# FTDI44.net
KiCad netlist of a schematic drawn in EAGLE
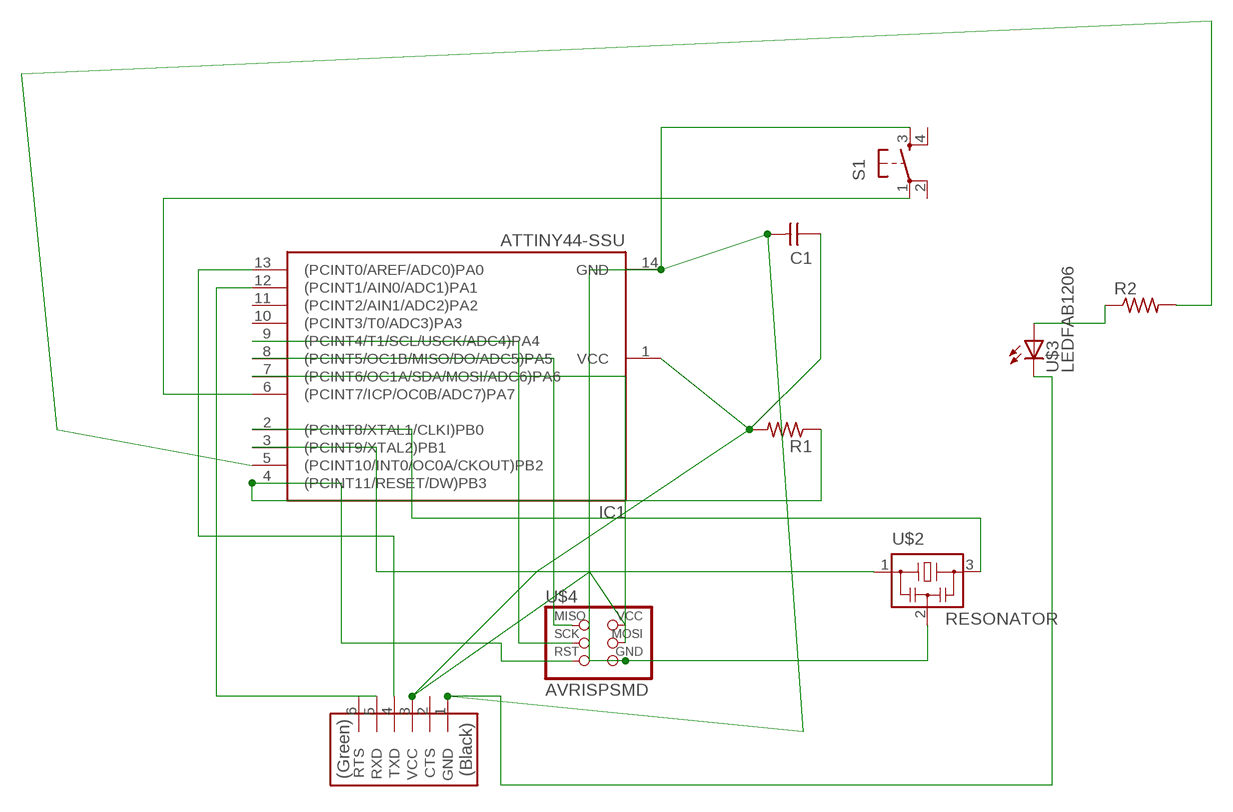
[diagram p0: schematic, sheet 1]

(export (version "E")
  (design (tool "Eeschema 10.0.6"))
  (components
    (comp (ref "C1")
      (value "CAP-UNPOLARIZEDFAB")
      (footprint "eagle-import:C1206FAB")
      (libsource (lib "eagle-import") (part "CAP-UNPOLARIZEDFAB"))
    )
    (comp (ref "IC1")
      (value "ATTINY44-SSU")
      (footprint "eagle-import:SOIC14")
      (libsource (lib "eagle-import") (part "ATTINY44-SSU"))
    )
    (comp (ref "R1")
      (value "RES-US1206FAB")
      (footprint "eagle-import:R1206FAB")
      (libsource (lib "eagle-import") (part "fab_RES-US1206FAB"))
    )
    (comp (ref "R2")
      (value "RES-US1206FAB")
      (footprint "eagle-import:R1206FAB")
      (libsource (lib "eagle-import") (part "RES-US1206FAB"))
    )
    (comp (ref "S1")
      (value "6MM_SWITCH6MM_SWITCH")
      (footprint "eagle-import:6MM_SWITCH")
      (libsource (lib "eagle-import") (part "6MM_SWITCH6MM_SWITCH"))
    )
    (comp (ref "U$1")
      (value "FTDI-SMD-HEADER")
      (footprint "eagle-import:1X06SMD")
      (libsource (lib "eagle-import") (part "FTDI-SMD-HEADER"))
    )
    (comp (ref "U$2")
      (value "RESONATOR")
      (footprint "eagle-import:EFOBM")
      (libsource (lib "eagle-import") (part "RESONATOR"))
    )
    (comp (ref "U$3")
      (value "LEDFAB1206")
      (footprint "eagle-import:LED1206FAB")
      (libsource (lib "eagle-import") (part "LEDFAB1206"))
    )
    (comp (ref "U$4")
      (value "AVRISPSMD")
      (footprint "eagle-import:2X03SMD")
      (libsource (lib "eagle-import") (part "AVRISPSMD"))
    )
  )
  (nets
    (net (code "1") (name "Net-(IC1-(PCINT0{slash}AREF{slash}ADC0)PA0)") (class "Default")
      (node (ref "IC1") (pin "13") (pinfunction "(PCINT0/AREF/ADC0)PA0_13") (pintype "bidirectional"))
      (node (ref "U$1") (pin "4") (pinfunction "TXD_4") (pintype "bidirectional"))
    )
    (net (code "2") (name "Net-(IC1-(PCINT1{slash}AIN0{slash}ADC1)PA1)") (class "Default")
      (node (ref "IC1") (pin "12") (pinfunction "(PCINT1/AIN0/ADC1)PA1_12") (pintype "bidirectional"))
      (node (ref "U$1") (pin "5") (pinfunction "RXD_5") (pintype "bidirectional"))
    )
    (net (code "3") (name "Net-(IC1-(PCINT4{slash}T1{slash}SCL{slash}USCK{slash}ADC4)PA4)") (class "Default")
      (node (ref "IC1") (pin "9") (pinfunction "(PCINT4/T1/SCL/USCK/ADC4)PA4_9") (pintype "bidirectional"))
      (node (ref "U$4") (pin "3") (pinfunction "SCK_3") (pintype "passive"))
    )
    (net (code "4") (name "Net-(IC1-(PCINT5{slash}OC1B{slash}MISO{slash}DO{slash}ADC5)PA5)") (class "Default")
      (node (ref "IC1") (pin "8") (pinfunction "(PCINT5/OC1B/MISO/DO/ADC5)PA5_8") (pintype "bidirectional"))
      (node (ref "U$4") (pin "1") (pinfunction "MISO_1") (pintype "passive"))
    )
    (net (code "5") (name "Net-(IC1-(PCINT6{slash}OC1A{slash}SDA{slash}MOSI{slash}ADC6)PA6)") (class "Default")
      (node (ref "IC1") (pin "7") (pinfunction "(PCINT6/OC1A/SDA/MOSI/ADC6)PA6_7") (pintype "bidirectional"))
      (node (ref "U$4") (pin "4") (pinfunction "MOSI_4") (pintype "passive"))
    )
    (net (code "6") (name "Net-(IC1-(PCINT7{slash}ICP{slash}OC0B{slash}ADC7)PA7)") (class "Default")
      (node (ref "IC1") (pin "6") (pinfunction "(PCINT7/ICP/OC0B/ADC7)PA7_6") (pintype "bidirectional"))
      (node (ref "S1") (pin "1") (pinfunction "P_1") (pintype "passive"))
    )
    (net (code "7") (name "Net-(IC1-(PCINT8{slash}XTAL1{slash}CLKI)PB0)") (class "Default")
      (node (ref "IC1") (pin "2") (pinfunction "(PCINT8/XTAL1/CLKI)PB0_2") (pintype "bidirectional"))
      (node (ref "U$2") (pin "3") (pinfunction "3_3") (pintype "passive"))
    )
    (net (code "8") (name "Net-(IC1-(PCINT9{slash}XTAL2)PB1)") (class "Default")
      (node (ref "IC1") (pin "3") (pinfunction "(PCINT9/XTAL2)PB1_3") (pintype "bidirectional"))
      (node (ref "U$2") (pin "1") (pinfunction "1_1") (pintype "passive"))
    )
    (net (code "9") (name "Net-(IC1-(PCINT10{slash}INT0{slash}OC0A{slash}CKOUT)PB2)") (class "Default")
      (node (ref "IC1") (pin "5") (pinfunction "(PCINT10/INT0/OC0A/CKOUT)PB2_5") (pintype "bidirectional"))
      (node (ref "R2") (pin "2") (pinfunction "2_2") (pintype "passive"))
    )
    (net (code "10") (name "Net-(IC1-(PCINT11{slash}RESET{slash}DW)PB3)") (class "Default")
      (node (ref "IC1") (pin "4") (pinfunction "(PCINT11/RESET/DW)PB3_4") (pintype "bidirectional"))
      (node (ref "R1") (pin "1") (pinfunction "1_1") (pintype "passive"))
      (node (ref "U$4") (pin "5") (pinfunction "RST_5") (pintype "passive"))
    )
    (net (code "11") (name "Net-(IC1-GND)") (class "Default")
      (node (ref "C1") (pin "2") (pinfunction "2_2") (pintype "passive"))
      (node (ref "IC1") (pin "14") (pinfunction "GND_14") (pintype "power_in"))
      (node (ref "S1") (pin "3") (pinfunction "S_3") (pintype "passive"))
      (node (ref "U$1") (pin "1") (pinfunction "GND_1") (pintype "bidirectional"))
      (node (ref "U$2") (pin "2") (pinfunction "2_2") (pintype "passive"))
      (node (ref "U$3") (pin "2") (pinfunction "C_2") (pintype "passive"))
      (node (ref "U$4") (pin "6") (pinfunction "GND_6") (pintype "passive"))
    )
    (net (code "12") (name "Net-(IC1-VCC)") (class "Default")
      (node (ref "C1") (pin "1") (pinfunction "1_1") (pintype "passive"))
      (node (ref "IC1") (pin "1") (pinfunction "VCC_1") (pintype "power_in"))
      (node (ref "R1") (pin "2") (pinfunction "2_2") (pintype "passive"))
      (node (ref "U$1") (pin "3") (pinfunction "VCC_3") (pintype "bidirectional"))
      (node (ref "U$4") (pin "2") (pinfunction "VCC_2") (pintype "passive"))
    )
    (net (code "13") (name "Net-(U$3-A)") (class "Default")
      (node (ref "R2") (pin "1") (pinfunction "1_1") (pintype "passive"))
      (node (ref "U$3") (pin "1") (pinfunction "A_1") (pintype "passive"))
    )
    (net (code "14") (name "unconnected-(IC1-(PCINT2{slash}AIN1{slash}ADC2)PA2-Pad11)") (class "Default")
      (node (ref "IC1") (pin "11") (pinfunction "(PCINT2/AIN1/ADC2)PA2_11") (pintype "bidirectional"))
    )
    (net (code "15") (name "unconnected-(IC1-(PCINT3{slash}T0{slash}ADC3)PA3-Pad10)") (class "Default")
      (node (ref "IC1") (pin "10") (pinfunction "(PCINT3/T0/ADC3)PA3_10") (pintype "bidirectional"))
    )
    (net (code "16") (name "unconnected-(S1-P1-Pad2)") (class "Default")
      (node (ref "S1") (pin "2") (pinfunction "P1_2") (pintype "passive"))
    )
    (net (code "17") (name "unconnected-(S1-S1-Pad4)") (class "Default")
      (node (ref "S1") (pin "4") (pinfunction "S1_4") (pintype "passive"))
    )
    (net (code "18") (name "unconnected-(U$1-CTS-Pad2)") (class "Default")
      (node (ref "U$1") (pin "2") (pinfunction "CTS_2") (pintype "bidirectional"))
    )
    (net (code "19") (name "unconnected-(U$1-RTS-Pad6)") (class "Default")
      (node (ref "U$1") (pin "6") (pinfunction "RTS_6") (pintype "bidirectional"))
    )
  )
)
